# 2_SensorArraySchematic.net
KiCad netlist of a schematic drawn in EasyEDA
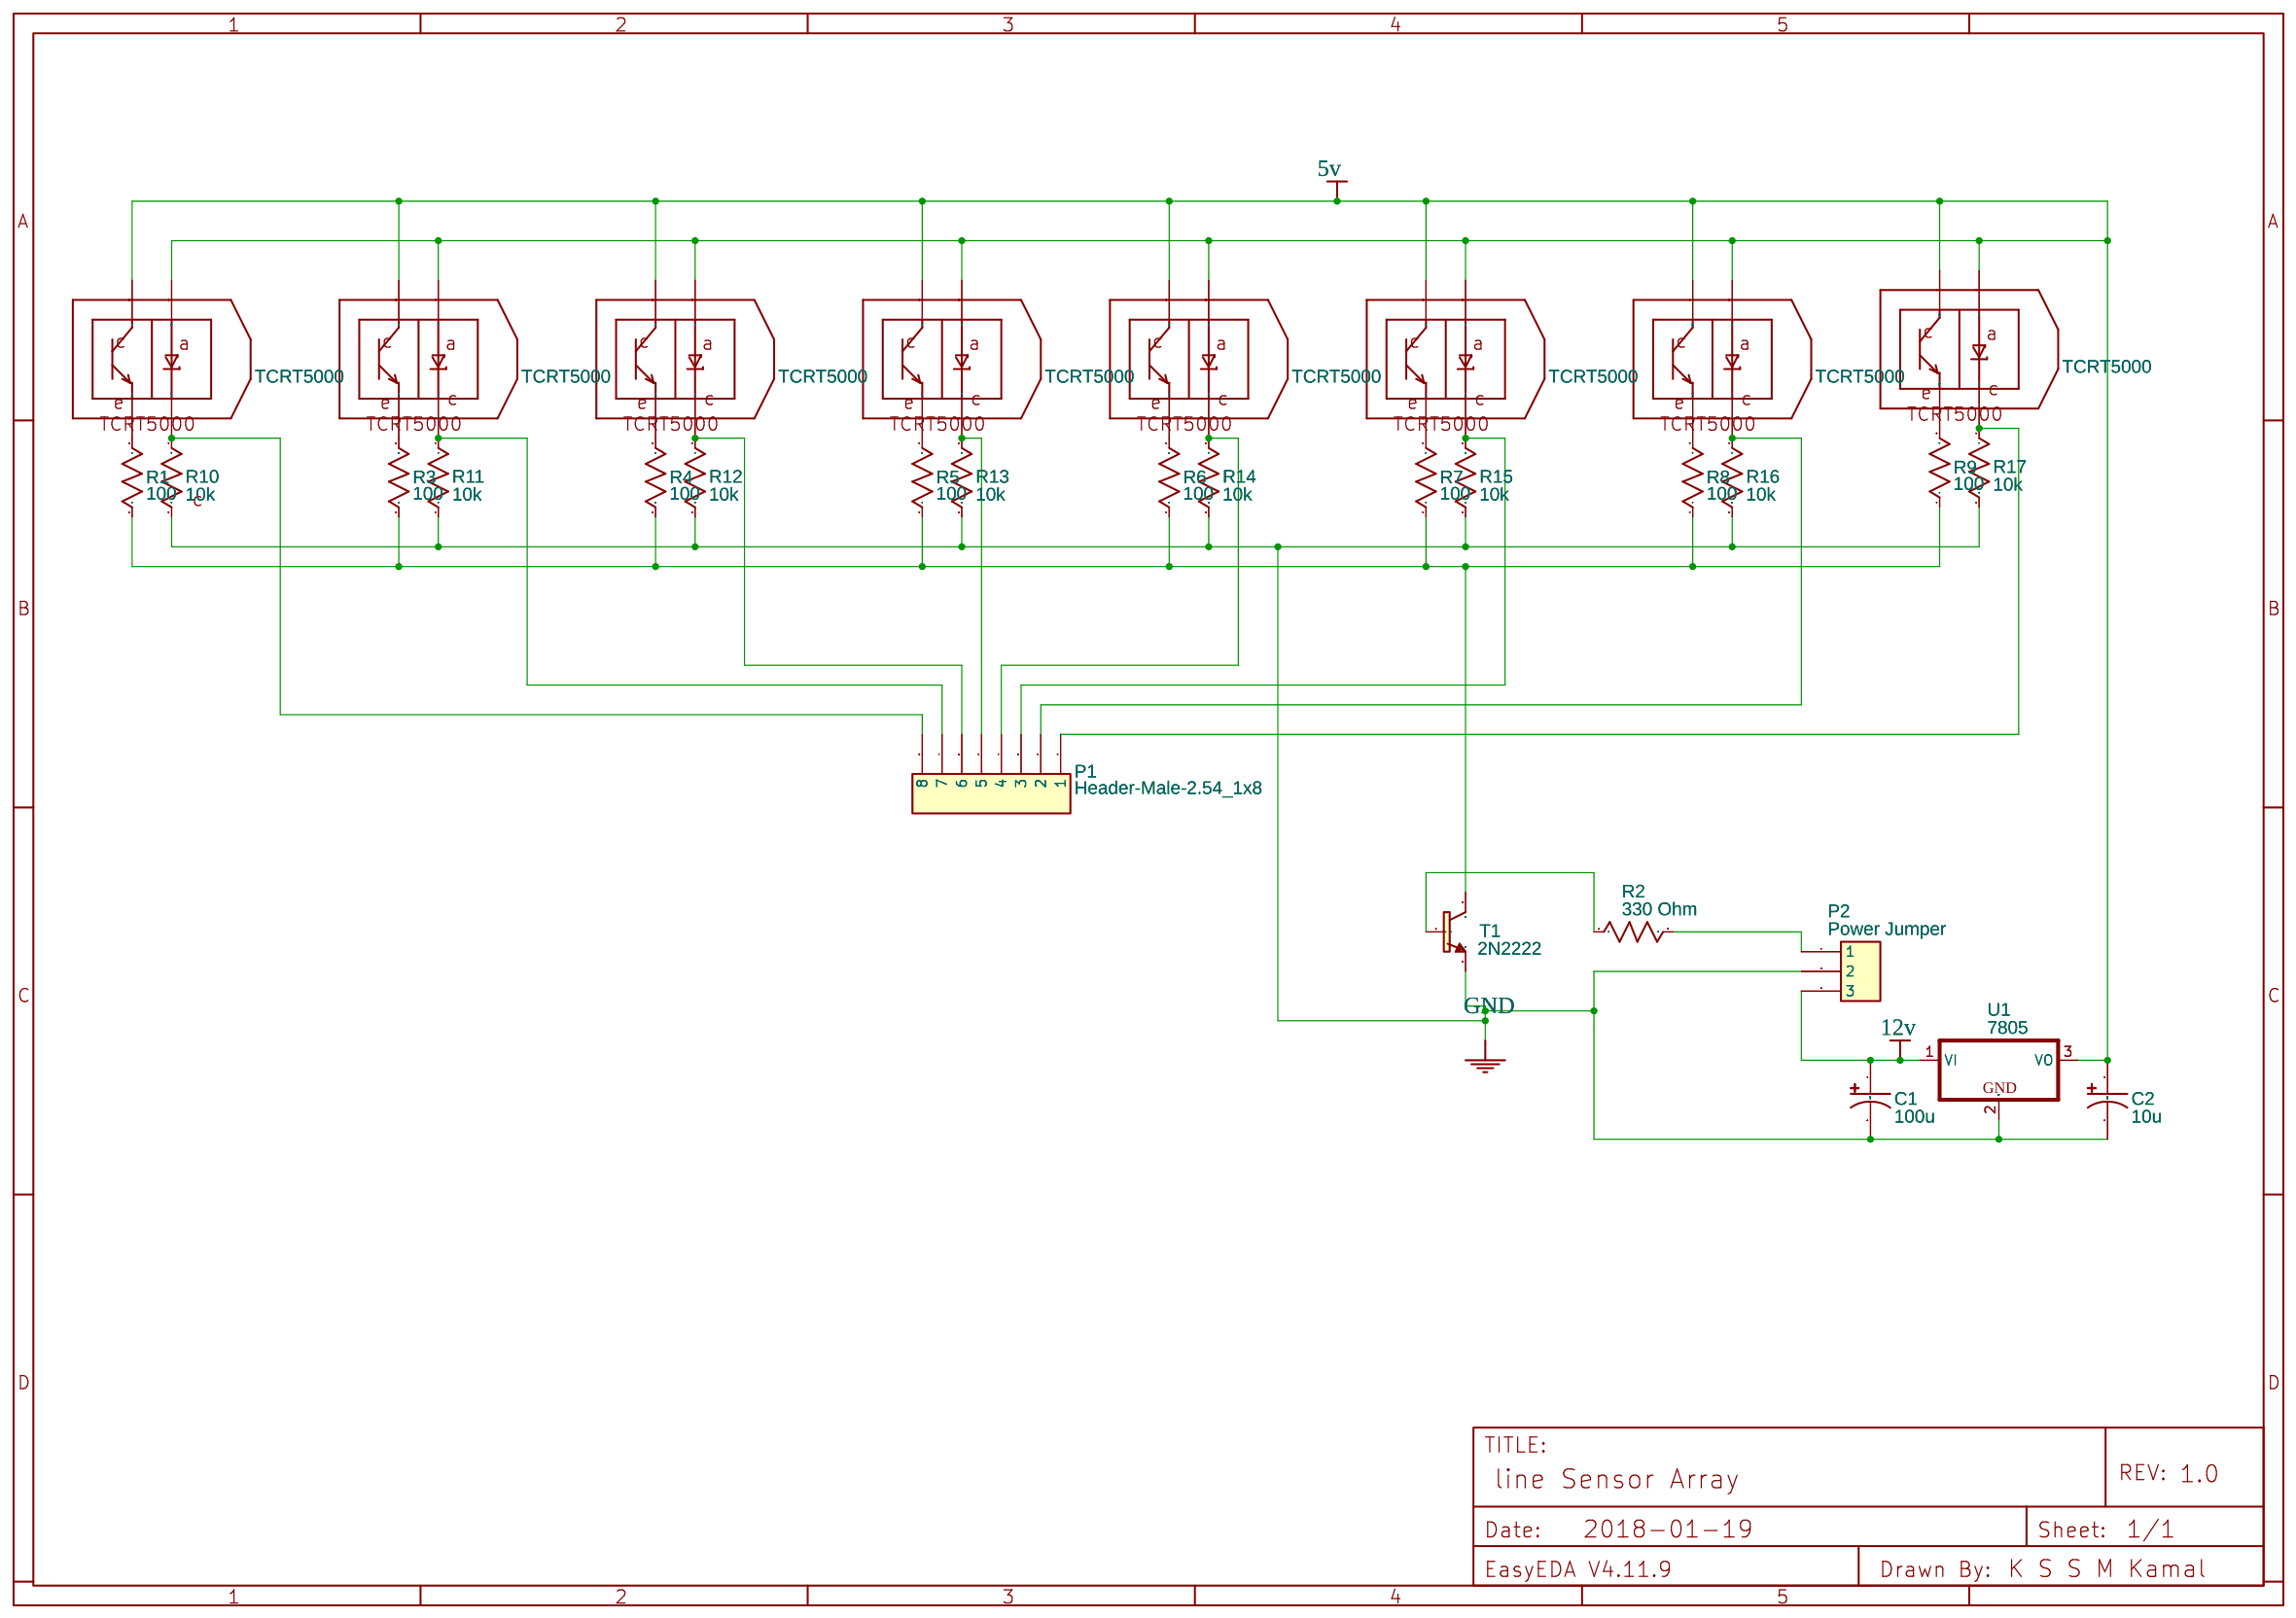
[diagram p0: schematic sheet]

(export (version "E")
  (design (tool "Eeschema 10.0.6"))
  (components
    (comp (ref "C1")
      (value "100u")
      (fields (field (name "BOM_Manufacturer Part") "?"))
      (libsource (lib "") (part "Capacitor"))
    )
    (comp (ref "C2")
      (value "10u")
      (fields (field (name "BOM_Manufacturer Part") "?"))
      (libsource (lib "") (part "Capacitor_1"))
    )
    (comp (ref "P1") (value "Header-Male-2.54_1x8") (libsource (lib "") (part "Unknown_495_380")))
    (comp (ref "P2")
      (value "Power Jumper")
      (fields (field (name "BOM_Manufacturer Part") "Header-Male-2.54_1x3"))
      (libsource (lib "") (part "Unknown_920_485"))
    )
    (comp (ref "R1")
      (value "100")
      (fields (field (name "BOM_Manufacturer Part") "?"))
      (libsource (lib "") (part "Resistor_1"))
    )
    (comp (ref "R2")
      (value "330 Ohm")
      (fields (field (name "BOM_Manufacturer Part") "?"))
      (libsource (lib "") (part "Resistor_2"))
    )
    (comp (ref "R3")
      (value "100")
      (fields (field (name "BOM_Manufacturer Part") "?"))
      (libsource (lib "") (part "Resistor_1"))
    )
    (comp (ref "R4")
      (value "100")
      (fields (field (name "BOM_Manufacturer Part") "?"))
      (libsource (lib "") (part "Resistor_1"))
    )
    (comp (ref "R5")
      (value "100")
      (fields (field (name "BOM_Manufacturer Part") "?"))
      (libsource (lib "") (part "Resistor_1"))
    )
    (comp (ref "R6")
      (value "100")
      (fields (field (name "BOM_Manufacturer Part") "?"))
      (libsource (lib "") (part "Resistor_1"))
    )
    (comp (ref "R7")
      (value "100")
      (fields (field (name "BOM_Manufacturer Part") "?"))
      (libsource (lib "") (part "Resistor_1"))
    )
    (comp (ref "R8")
      (value "100")
      (fields (field (name "BOM_Manufacturer Part") "?"))
      (libsource (lib "") (part "Resistor_1"))
    )
    (comp (ref "R9")
      (value "100")
      (fields (field (name "BOM_Manufacturer Part") "?"))
      (libsource (lib "") (part "Resistor_1"))
    )
    (comp (ref "R10")
      (value "10k")
      (fields (field (name "BOM_Manufacturer Part") "?"))
      (libsource (lib "") (part "Resistor"))
    )
    (comp (ref "R11")
      (value "10k")
      (fields (field (name "BOM_Manufacturer Part") "?"))
      (libsource (lib "") (part "Resistor"))
    )
    (comp (ref "R12")
      (value "10k")
      (fields (field (name "BOM_Manufacturer Part") "?"))
      (libsource (lib "") (part "Resistor"))
    )
    (comp (ref "R13")
      (value "10k")
      (fields (field (name "BOM_Manufacturer Part") "?"))
      (libsource (lib "") (part "Resistor"))
    )
    (comp (ref "R14")
      (value "10k")
      (fields (field (name "BOM_Manufacturer Part") "?"))
      (libsource (lib "") (part "Resistor"))
    )
    (comp (ref "R15")
      (value "10k")
      (fields (field (name "BOM_Manufacturer Part") "?"))
      (libsource (lib "") (part "Resistor"))
    )
    (comp (ref "R16")
      (value "10k")
      (fields (field (name "BOM_Manufacturer Part") "?"))
      (libsource (lib "") (part "Resistor"))
    )
    (comp (ref "R17")
      (value "10k")
      (fields (field (name "BOM_Manufacturer Part") "?"))
      (libsource (lib "") (part "Resistor"))
    )
    (comp (ref "S1")
      (value "TCRT5000")
      (fields (field (name "BOM_Manufacturer Part") "?"))
      (libsource (lib "") (part "Unknown_70_175"))
    )
    (comp (ref "S2")
      (value "TCRT5000")
      (fields (field (name "BOM_Manufacturer Part") "?"))
      (libsource (lib "") (part "Unknown_205_175"))
    )
    (comp (ref "S3")
      (value "TCRT5000")
      (fields (field (name "BOM_Manufacturer Part") "?"))
      (libsource (lib "") (part "Unknown_335_175"))
    )
    (comp (ref "S4")
      (value "TCRT5000")
      (fields (field (name "BOM_Manufacturer Part") "?"))
      (libsource (lib "") (part "Unknown_470_175"))
    )
    (comp (ref "S5")
      (value "TCRT5000")
      (fields (field (name "BOM_Manufacturer Part") "?"))
      (libsource (lib "") (part "Unknown_595_175"))
    )
    (comp (ref "S6")
      (value "TCRT5000")
      (fields (field (name "BOM_Manufacturer Part") "?"))
      (libsource (lib "") (part "Unknown_725_175"))
    )
    (comp (ref "S7")
      (value "TCRT5000")
      (fields (field (name "BOM_Manufacturer Part") "?"))
      (libsource (lib "") (part "Unknown_860_175"))
    )
    (comp (ref "S8")
      (value "TCRT5000")
      (fields (field (name "BOM_Manufacturer Part") "?"))
      (libsource (lib "") (part "Unknown_985_170"))
    )
    (comp (ref "T1")
      (value "2N2222")
      (fields (field (name "BOM_Manufacturer Part") "?"))
      (libsource (lib "") (part "Unknown_725_465"))
    )
    (comp (ref "U1")
      (value "7805")
      (fields (field (name "BOM_Manufacturer Part") "?"))
      (libsource (lib "") (part "Unknown_1005_530"))
    )
  )
  (nets
    (net (code "1") (name "5v") (class "Default")
      (node (ref "C2") (pin "1") (pinfunction "1_1") (pintype "unspecified"))
      (node (ref "S1") (pin "P$1") (pinfunction "P$1_P$1") (pintype "unspecified"))
      (node (ref "S1") (pin "P$3") (pinfunction "P$3_P$3") (pintype "unspecified"))
      (node (ref "S2") (pin "P$1") (pinfunction "P$1_P$1") (pintype "unspecified"))
      (node (ref "S2") (pin "P$3") (pinfunction "P$3_P$3") (pintype "unspecified"))
      (node (ref "S3") (pin "P$1") (pinfunction "P$1_P$1") (pintype "unspecified"))
      (node (ref "S3") (pin "P$3") (pinfunction "P$3_P$3") (pintype "unspecified"))
      (node (ref "S4") (pin "P$1") (pinfunction "P$1_P$1") (pintype "unspecified"))
      (node (ref "S4") (pin "P$3") (pinfunction "P$3_P$3") (pintype "unspecified"))
      (node (ref "S5") (pin "P$1") (pinfunction "P$1_P$1") (pintype "unspecified"))
      (node (ref "S5") (pin "P$3") (pinfunction "P$3_P$3") (pintype "unspecified"))
      (node (ref "S6") (pin "P$1") (pinfunction "P$1_P$1") (pintype "unspecified"))
      (node (ref "S6") (pin "P$3") (pinfunction "P$3_P$3") (pintype "unspecified"))
      (node (ref "S7") (pin "P$1") (pinfunction "P$1_P$1") (pintype "unspecified"))
      (node (ref "S7") (pin "P$3") (pinfunction "P$3_P$3") (pintype "unspecified"))
      (node (ref "S8") (pin "P$1") (pinfunction "P$1_P$1") (pintype "unspecified"))
      (node (ref "S8") (pin "P$3") (pinfunction "P$3_P$3") (pintype "unspecified"))
      (node (ref "U1") (pin "3") (pinfunction "VO_3") (pintype "unspecified"))
    )
    (net (code "2") (name "12v") (class "Default")
      (node (ref "C1") (pin "1") (pinfunction "1_1") (pintype "unspecified"))
      (node (ref "P2") (pin "3") (pinfunction "3_3") (pintype "input"))
      (node (ref "U1") (pin "1") (pinfunction "VI_1") (pintype "input"))
    )
    (net (code "3") (name "GND") (class "Default")
      (node (ref "C1") (pin "2") (pinfunction "2_2") (pintype "unspecified"))
      (node (ref "C2") (pin "2") (pinfunction "2_2") (pintype "unspecified"))
      (node (ref "P2") (pin "2") (pinfunction "2_2") (pintype "input"))
      (node (ref "R10") (pin "2") (pinfunction "2_2") (pintype "unspecified"))
      (node (ref "R11") (pin "2") (pinfunction "2_2") (pintype "unspecified"))
      (node (ref "R12") (pin "2") (pinfunction "2_2") (pintype "unspecified"))
      (node (ref "R13") (pin "2") (pinfunction "2_2") (pintype "unspecified"))
      (node (ref "R14") (pin "2") (pinfunction "2_2") (pintype "unspecified"))
      (node (ref "R15") (pin "2") (pinfunction "2_2") (pintype "unspecified"))
      (node (ref "R16") (pin "2") (pinfunction "2_2") (pintype "unspecified"))
      (node (ref "R17") (pin "2") (pinfunction "2_2") (pintype "unspecified"))
      (node (ref "T1") (pin "E") (pinfunction "E_E") (pintype "unspecified"))
      (node (ref "U1") (pin "2") (pinfunction "GND_2") (pintype "unspecified"))
    )
    (net (code "4") (name "Net-(P1-Pad1)") (class "Default")
      (node (ref "P1") (pin "1") (pinfunction "1_1") (pintype "input"))
      (node (ref "R17") (pin "1") (pinfunction "1_1") (pintype "unspecified"))
      (node (ref "S8") (pin "P$4") (pinfunction "P$4_P$4") (pintype "unspecified"))
    )
    (net (code "5") (name "Net-(P1-Pad2)") (class "Default")
      (node (ref "P1") (pin "2") (pinfunction "2_2") (pintype "input"))
      (node (ref "R16") (pin "1") (pinfunction "1_1") (pintype "unspecified"))
      (node (ref "S7") (pin "P$4") (pinfunction "P$4_P$4") (pintype "unspecified"))
    )
    (net (code "6") (name "Net-(P1-Pad3)") (class "Default")
      (node (ref "P1") (pin "3") (pinfunction "3_3") (pintype "input"))
      (node (ref "R15") (pin "1") (pinfunction "1_1") (pintype "unspecified"))
      (node (ref "S6") (pin "P$4") (pinfunction "P$4_P$4") (pintype "unspecified"))
    )
    (net (code "7") (name "Net-(P1-Pad4)") (class "Default")
      (node (ref "P1") (pin "4") (pinfunction "4_4") (pintype "input"))
      (node (ref "R14") (pin "1") (pinfunction "1_1") (pintype "unspecified"))
      (node (ref "S5") (pin "P$4") (pinfunction "P$4_P$4") (pintype "unspecified"))
    )
    (net (code "8") (name "Net-(P1-Pad5)") (class "Default")
      (node (ref "P1") (pin "5") (pinfunction "5_5") (pintype "input"))
      (node (ref "R13") (pin "1") (pinfunction "1_1") (pintype "unspecified"))
      (node (ref "S4") (pin "P$4") (pinfunction "P$4_P$4") (pintype "unspecified"))
    )
    (net (code "9") (name "Net-(P1-Pad6)") (class "Default")
      (node (ref "P1") (pin "6") (pinfunction "6_6") (pintype "input"))
      (node (ref "R12") (pin "1") (pinfunction "1_1") (pintype "unspecified"))
      (node (ref "S3") (pin "P$4") (pinfunction "P$4_P$4") (pintype "unspecified"))
    )
    (net (code "10") (name "Net-(P1-Pad7)") (class "Default")
      (node (ref "P1") (pin "7") (pinfunction "7_7") (pintype "input"))
      (node (ref "R11") (pin "1") (pinfunction "1_1") (pintype "unspecified"))
      (node (ref "S2") (pin "P$4") (pinfunction "P$4_P$4") (pintype "unspecified"))
    )
    (net (code "11") (name "Net-(P1-Pad8)") (class "Default")
      (node (ref "P1") (pin "8") (pinfunction "8_8") (pintype "input"))
      (node (ref "R10") (pin "1") (pinfunction "1_1") (pintype "unspecified"))
      (node (ref "S1") (pin "P$4") (pinfunction "P$4_P$4") (pintype "unspecified"))
    )
    (net (code "12") (name "Net-(P2-Pad1)") (class "Default")
      (node (ref "P2") (pin "1") (pinfunction "1_1") (pintype "input"))
      (node (ref "R2") (pin "2") (pinfunction "2_2") (pintype "unspecified"))
    )
    (net (code "13") (name "Net-(R1-Pad1)") (class "Default")
      (node (ref "R1") (pin "1") (pinfunction "1_1") (pintype "unspecified"))
      (node (ref "R3") (pin "1") (pinfunction "1_1") (pintype "unspecified"))
      (node (ref "R4") (pin "1") (pinfunction "1_1") (pintype "unspecified"))
      (node (ref "R5") (pin "1") (pinfunction "1_1") (pintype "unspecified"))
      (node (ref "R6") (pin "1") (pinfunction "1_1") (pintype "unspecified"))
      (node (ref "R7") (pin "1") (pinfunction "1_1") (pintype "unspecified"))
      (node (ref "R8") (pin "1") (pinfunction "1_1") (pintype "unspecified"))
      (node (ref "R9") (pin "1") (pinfunction "1_1") (pintype "unspecified"))
      (node (ref "T1") (pin "C") (pinfunction "C_C") (pintype "unspecified"))
    )
    (net (code "14") (name "Net-(R1-Pad2)") (class "Default")
      (node (ref "R1") (pin "2") (pinfunction "2_2") (pintype "unspecified"))
      (node (ref "S1") (pin "P$2") (pinfunction "P$2_P$2") (pintype "unspecified"))
    )
    (net (code "15") (name "Net-(R2-Pad1)") (class "Default")
      (node (ref "R2") (pin "1") (pinfunction "1_1") (pintype "unspecified"))
      (node (ref "T1") (pin "B") (pinfunction "B_B") (pintype "unspecified"))
    )
    (net (code "16") (name "Net-(R3-Pad2)") (class "Default")
      (node (ref "R3") (pin "2") (pinfunction "2_2") (pintype "unspecified"))
      (node (ref "S2") (pin "P$2") (pinfunction "P$2_P$2") (pintype "unspecified"))
    )
    (net (code "17") (name "Net-(R4-Pad2)") (class "Default")
      (node (ref "R4") (pin "2") (pinfunction "2_2") (pintype "unspecified"))
      (node (ref "S3") (pin "P$2") (pinfunction "P$2_P$2") (pintype "unspecified"))
    )
    (net (code "18") (name "Net-(R5-Pad2)") (class "Default")
      (node (ref "R5") (pin "2") (pinfunction "2_2") (pintype "unspecified"))
      (node (ref "S4") (pin "P$2") (pinfunction "P$2_P$2") (pintype "unspecified"))
    )
    (net (code "19") (name "Net-(R6-Pad2)") (class "Default")
      (node (ref "R6") (pin "2") (pinfunction "2_2") (pintype "unspecified"))
      (node (ref "S5") (pin "P$2") (pinfunction "P$2_P$2") (pintype "unspecified"))
    )
    (net (code "20") (name "Net-(R7-Pad2)") (class "Default")
      (node (ref "R7") (pin "2") (pinfunction "2_2") (pintype "unspecified"))
      (node (ref "S6") (pin "P$2") (pinfunction "P$2_P$2") (pintype "unspecified"))
    )
    (net (code "21") (name "Net-(R8-Pad2)") (class "Default")
      (node (ref "R8") (pin "2") (pinfunction "2_2") (pintype "unspecified"))
      (node (ref "S7") (pin "P$2") (pinfunction "P$2_P$2") (pintype "unspecified"))
    )
    (net (code "22") (name "Net-(R9-Pad2)") (class "Default")
      (node (ref "R9") (pin "2") (pinfunction "2_2") (pintype "unspecified"))
      (node (ref "S8") (pin "P$2") (pinfunction "P$2_P$2") (pintype "unspecified"))
    )
  )
)
